# XBee_Pro_Shield.net
KiCad netlist of a schematic drawn in EAGLE
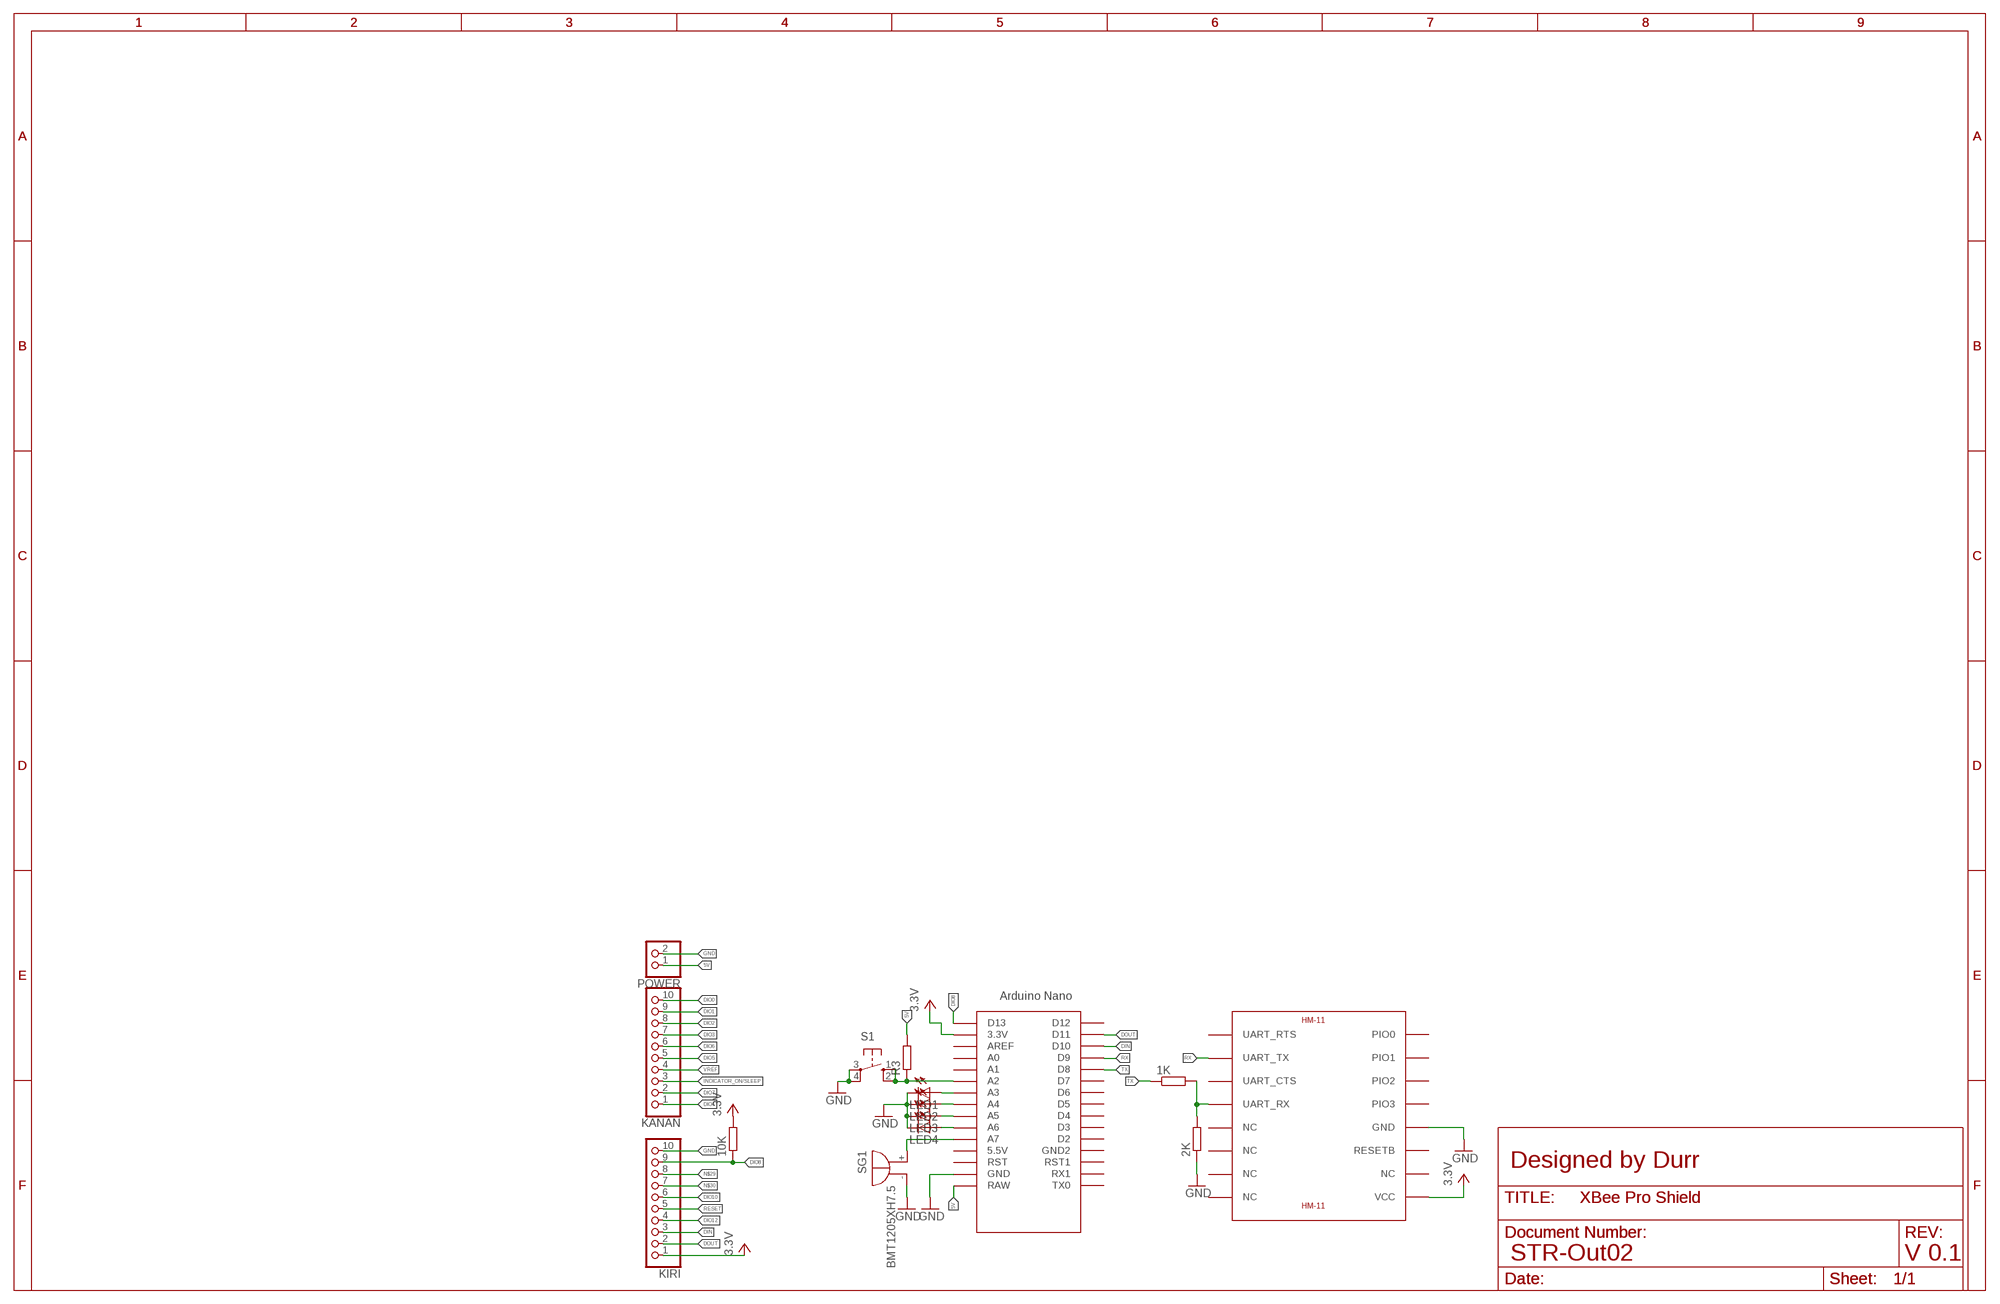
[diagram p0: schematic, sheet 1]

(export (version "E")
  (design (tool "Eeschema 10.0.6"))
  (components
    (comp (ref "1K")
      (value "R-EU_R1206")
      (footprint "eagle-import:R1206")
      (libsource (lib "eagle-import") (part "R-EU_R1206"))
    )
    (comp (ref "2K")
      (value "R-EU_R1206")
      (footprint "eagle-import:R1206")
      (libsource (lib "eagle-import") (part "R-EU_R1206"))
    )
    (comp (ref "10K")
      (value "R-EU_R1206")
      (footprint "eagle-import:R1206")
      (libsource (lib "eagle-import") (part "R-EU_R1206"))
    )
    (comp (ref "KANAN")
      (value "PINHD-1X10")
      (footprint "eagle-import:1X10")
      (libsource (lib "eagle-import") (part "PINHD-1X10"))
    )
    (comp (ref "KIRI")
      (value "PINHD-1X10")
      (footprint "eagle-import:1X10")
      (libsource (lib "eagle-import") (part "PINHD-1X10"))
    )
    (comp (ref "LED1")
      (value "LED5MM")
      (footprint "eagle-import:LED5MM")
      (libsource (lib "eagle-import") (part "LED5MM"))
    )
    (comp (ref "LED2")
      (value "LED5MM")
      (footprint "eagle-import:LED5MM")
      (libsource (lib "eagle-import") (part "LED5MM"))
    )
    (comp (ref "LED3")
      (value "LED5MM")
      (footprint "eagle-import:LED5MM")
      (libsource (lib "eagle-import") (part "LED5MM"))
    )
    (comp (ref "LED4")
      (value "LED5MM")
      (footprint "eagle-import:LED5MM")
      (libsource (lib "eagle-import") (part "LED5MM"))
    )
    (comp (ref "POWER")
      (value "PINHD-1X2")
      (footprint "eagle-import:1X02")
      (libsource (lib "eagle-import") (part "PINHD-1X2"))
    )
    (comp (ref "R3")
      (value "R-EU_R1206")
      (footprint "eagle-import:R1206")
      (libsource (lib "eagle-import") (part "R-EU_R1206"))
    )
    (comp (ref "S1")
      (value "40-XX")
      (footprint "eagle-import:B3F-40XX")
      (fields (field (name "MF") "OMRON COMPONENTS USA") (field (name "MPN") "B3F-4000"))
      (libsource (lib "eagle-import") (part "40-XX"))
    )
    (comp (ref "SG1")
      (value "BMT1205XH7.5")
      (footprint "eagle-import:BMT1205XH7.5")
      (libsource (lib "eagle-import") (part "BMT1205XH7.5"))
    )
    (comp (ref "U$1")
      (value "HM-11")
      (footprint "eagle-import:HM-11")
      (libsource (lib "eagle-import") (part "HM-11"))
    )
    (comp (ref "U$2")
      (value "NANO")
      (footprint "eagle-import:NANO")
      (libsource (lib "eagle-import") (part "NANO"))
    )
  )
  (nets
    (net (code "1") (name "3.3V") (class "Default")
      (node (ref "10K") (pin "2") (pinfunction "2_2") (pintype "passive"))
      (node (ref "KIRI") (pin "1") (pinfunction "1_1") (pintype "passive"))
      (node (ref "U$1") (pin "VCC") (pinfunction "VCC_VCC") (pintype "bidirectional"))
      (node (ref "U$2") (pin "3.3V") (pinfunction "3.3V_3.3V") (pintype "bidirectional"))
    )
    (net (code "2") (name "5V") (class "Default")
      (node (ref "POWER") (pin "1") (pinfunction "1_1") (pintype "passive"))
      (node (ref "R3") (pin "2") (pinfunction "2_2") (pintype "passive"))
      (node (ref "U$2") (pin "RAW") (pinfunction "RAW_RAW") (pintype "bidirectional"))
    )
    (net (code "3") (name "DIN") (class "Default")
      (node (ref "KIRI") (pin "3") (pinfunction "3_3") (pintype "passive"))
      (node (ref "U$2") (pin "D10") (pinfunction "D10_D10") (pintype "bidirectional"))
    )
    (net (code "4") (name "DIO0") (class "Default")
      (node (ref "KANAN") (pin "10") (pinfunction "10_10") (pintype "passive"))
    )
    (net (code "5") (name "DIO1") (class "Default")
      (node (ref "KANAN") (pin "9") (pinfunction "9_9") (pintype "passive"))
    )
    (net (code "6") (name "DIO2") (class "Default")
      (node (ref "KANAN") (pin "8") (pinfunction "8_8") (pintype "passive"))
    )
    (net (code "7") (name "DIO3") (class "Default")
      (node (ref "KANAN") (pin "7") (pinfunction "7_7") (pintype "passive"))
    )
    (net (code "8") (name "DIO4") (class "Default")
      (node (ref "KANAN") (pin "1") (pinfunction "1_1") (pintype "passive"))
    )
    (net (code "9") (name "DIO5") (class "Default")
      (node (ref "KANAN") (pin "5") (pinfunction "5_5") (pintype "passive"))
    )
    (net (code "10") (name "DIO6") (class "Default")
      (node (ref "KANAN") (pin "6") (pinfunction "6_6") (pintype "passive"))
    )
    (net (code "11") (name "DIO7") (class "Default")
      (node (ref "KANAN") (pin "2") (pinfunction "2_2") (pintype "passive"))
    )
    (net (code "12") (name "DIO8") (class "Default")
      (node (ref "10K") (pin "1") (pinfunction "1_1") (pintype "passive"))
      (node (ref "KIRI") (pin "9") (pinfunction "9_9") (pintype "passive"))
      (node (ref "U$2") (pin "D13") (pinfunction "D13_D13") (pintype "bidirectional"))
    )
    (net (code "13") (name "DIO10") (class "Default")
      (node (ref "KIRI") (pin "6") (pinfunction "6_6") (pintype "passive"))
    )
    (net (code "14") (name "DIO12") (class "Default")
      (node (ref "KIRI") (pin "4") (pinfunction "4_4") (pintype "passive"))
    )
    (net (code "15") (name "DOUT") (class "Default")
      (node (ref "KIRI") (pin "2") (pinfunction "2_2") (pintype "passive"))
      (node (ref "U$2") (pin "D11") (pinfunction "D11_D11") (pintype "bidirectional"))
    )
    (net (code "16") (name "GND") (class "Default")
      (node (ref "2K") (pin "1") (pinfunction "1_1") (pintype "passive"))
      (node (ref "KIRI") (pin "10") (pinfunction "10_10") (pintype "passive"))
      (node (ref "LED1") (pin "K") (pinfunction "C_K") (pintype "passive"))
      (node (ref "LED2") (pin "K") (pinfunction "C_K") (pintype "passive"))
      (node (ref "LED3") (pin "K") (pinfunction "C_K") (pintype "passive"))
      (node (ref "LED4") (pin "K") (pinfunction "C_K") (pintype "passive"))
      (node (ref "POWER") (pin "2") (pinfunction "2_2") (pintype "passive"))
      (node (ref "S1") (pin "3") (pinfunction "P_3") (pintype "passive"))
      (node (ref "S1") (pin "4") (pinfunction "P1_4") (pintype "passive"))
      (node (ref "SG1") (pin "-") (pinfunction "-_-") (pintype "passive"))
      (node (ref "U$1") (pin "GND") (pinfunction "GND_GND") (pintype "bidirectional"))
      (node (ref "U$2") (pin "GND") (pinfunction "GND_GND") (pintype "bidirectional"))
    )
    (net (code "17") (name "INDICATOR_ON{slash}SLEEP") (class "Default")
      (node (ref "KANAN") (pin "3") (pinfunction "3_3") (pintype "passive"))
    )
    (net (code "18") (name "N$29") (class "Default")
      (node (ref "KIRI") (pin "8") (pinfunction "8_8") (pintype "passive"))
    )
    (net (code "19") (name "N$30") (class "Default")
      (node (ref "KIRI") (pin "7") (pinfunction "7_7") (pintype "passive"))
    )
    (net (code "20") (name "Net-(1K-Pad2)") (class "Default")
      (node (ref "1K") (pin "2") (pinfunction "2_2") (pintype "passive"))
      (node (ref "2K") (pin "2") (pinfunction "2_2") (pintype "passive"))
      (node (ref "U$1") (pin "UART_RX") (pinfunction "UART_RX_UART_RX") (pintype "bidirectional"))
    )
    (net (code "21") (name "Net-(LED1-PadA)") (class "Default")
      (node (ref "LED1") (pin "A") (pinfunction "A_A") (pintype "passive"))
      (node (ref "U$2") (pin "A3") (pinfunction "A3_A3") (pintype "bidirectional"))
    )
    (net (code "22") (name "Net-(LED2-PadA)") (class "Default")
      (node (ref "LED2") (pin "A") (pinfunction "A_A") (pintype "passive"))
      (node (ref "U$2") (pin "A4") (pinfunction "A4_A4") (pintype "bidirectional"))
    )
    (net (code "23") (name "Net-(LED3-PadA)") (class "Default")
      (node (ref "LED3") (pin "A") (pinfunction "A_A") (pintype "passive"))
      (node (ref "U$2") (pin "A5") (pinfunction "A5_A5") (pintype "bidirectional"))
    )
    (net (code "24") (name "Net-(LED4-PadA)") (class "Default")
      (node (ref "LED4") (pin "A") (pinfunction "A_A") (pintype "passive"))
      (node (ref "U$2") (pin "A6") (pinfunction "A6_A6") (pintype "bidirectional"))
    )
    (net (code "25") (name "Net-(S1-S)") (class "Default")
      (node (ref "R3") (pin "1") (pinfunction "1_1") (pintype "passive"))
      (node (ref "S1") (pin "1") (pinfunction "S_1") (pintype "passive"))
      (node (ref "S1") (pin "2") (pinfunction "S1_2") (pintype "passive"))
      (node (ref "U$2") (pin "A2") (pinfunction "A2_A2") (pintype "bidirectional"))
    )
    (net (code "26") (name "Net-(SG1-Pad+)") (class "Default")
      (node (ref "SG1") (pin "+") (pinfunction "+_+") (pintype "passive"))
      (node (ref "U$2") (pin "A7") (pinfunction "A7_A7") (pintype "bidirectional"))
    )
    (net (code "27") (name "RESET") (class "Default")
      (node (ref "KIRI") (pin "5") (pinfunction "5_5") (pintype "passive"))
    )
    (net (code "28") (name "RX") (class "Default")
      (node (ref "U$1") (pin "UART_TX") (pinfunction "UART_TX_UART_TX") (pintype "bidirectional"))
      (node (ref "U$2") (pin "D9") (pinfunction "D9_D9") (pintype "bidirectional"))
    )
    (net (code "29") (name "TX") (class "Default")
      (node (ref "1K") (pin "1") (pinfunction "1_1") (pintype "passive"))
      (node (ref "U$2") (pin "D8") (pinfunction "D8_D8") (pintype "bidirectional"))
    )
    (net (code "30") (name "VREF") (class "Default")
      (node (ref "KANAN") (pin "4") (pinfunction "4_4") (pintype "passive"))
    )
    (net (code "31") (name "unconnected-(U$1-NC-PadNC@5)") (class "Default")
      (node (ref "U$1") (pin "NC@5") (pinfunction "NC_NC@5") (pintype "bidirectional"))
    )
    (net (code "32") (name "unconnected-(U$1-NC-PadNC@6)") (class "Default")
      (node (ref "U$1") (pin "NC@6") (pinfunction "NC_NC@6") (pintype "bidirectional"))
    )
    (net (code "33") (name "unconnected-(U$1-NC-PadNC@7)") (class "Default")
      (node (ref "U$1") (pin "NC@7") (pinfunction "NC_NC@7") (pintype "bidirectional"))
    )
    (net (code "34") (name "unconnected-(U$1-NC-PadNC@8)") (class "Default")
      (node (ref "U$1") (pin "NC@8") (pinfunction "NC_NC@8") (pintype "bidirectional"))
    )
    (net (code "35") (name "unconnected-(U$1-NC-PadNC@10)") (class "Default")
      (node (ref "U$1") (pin "NC@10") (pinfunction "NC_NC@10") (pintype "bidirectional"))
    )
    (net (code "36") (name "unconnected-(U$1-PadPIO0)") (class "Default")
      (node (ref "U$1") (pin "PIO0") (pinfunction "PIO0_PIO0") (pintype "bidirectional"))
    )
    (net (code "37") (name "unconnected-(U$1-PadPIO1)") (class "Default")
      (node (ref "U$1") (pin "PIO1") (pinfunction "PIO1_PIO1") (pintype "bidirectional"))
    )
    (net (code "38") (name "unconnected-(U$1-PadPIO2)") (class "Default")
      (node (ref "U$1") (pin "PIO2") (pinfunction "PIO2_PIO2") (pintype "bidirectional"))
    )
    (net (code "39") (name "unconnected-(U$1-PadPIO3)") (class "Default")
      (node (ref "U$1") (pin "PIO3") (pinfunction "PIO3_PIO3") (pintype "bidirectional"))
    )
    (net (code "40") (name "unconnected-(U$1-PadRESETB)") (class "Default")
      (node (ref "U$1") (pin "RESETB") (pinfunction "RESETB_RESETB") (pintype "bidirectional"))
    )
    (net (code "41") (name "unconnected-(U$1-PadUART_CTS)") (class "Default")
      (node (ref "U$1") (pin "UART_CTS") (pinfunction "UART_CTS_UART_CTS") (pintype "bidirectional"))
    )
    (net (code "42") (name "unconnected-(U$1-PadUART_RTS)") (class "Default")
      (node (ref "U$1") (pin "UART_RTS") (pinfunction "UART_RTS_UART_RTS") (pintype "bidirectional"))
    )
    (net (code "43") (name "unconnected-(U$2-5.5V-Pad5V)") (class "Default")
      (node (ref "U$2") (pin "5V") (pinfunction "5.5V_5V") (pintype "bidirectional"))
    )
    (net (code "44") (name "unconnected-(U$2-GND2-PadGND1)") (class "Default")
      (node (ref "U$2") (pin "GND1") (pinfunction "GND2_GND1") (pintype "bidirectional"))
    )
    (net (code "45") (name "unconnected-(U$2-PadA0)") (class "Default")
      (node (ref "U$2") (pin "A0") (pinfunction "A0_A0") (pintype "bidirectional"))
    )
    (net (code "46") (name "unconnected-(U$2-PadA1)") (class "Default")
      (node (ref "U$2") (pin "A1") (pinfunction "A1_A1") (pintype "bidirectional"))
    )
    (net (code "47") (name "unconnected-(U$2-PadAREF)") (class "Default")
      (node (ref "U$2") (pin "AREF") (pinfunction "AREF_AREF") (pintype "bidirectional"))
    )
    (net (code "48") (name "unconnected-(U$2-PadD2)") (class "Default")
      (node (ref "U$2") (pin "D2") (pinfunction "D2_D2") (pintype "bidirectional"))
    )
    (net (code "49") (name "unconnected-(U$2-PadD3)") (class "Default")
      (node (ref "U$2") (pin "D3") (pinfunction "D3_D3") (pintype "bidirectional"))
    )
    (net (code "50") (name "unconnected-(U$2-PadD4)") (class "Default")
      (node (ref "U$2") (pin "D4") (pinfunction "D4_D4") (pintype "bidirectional"))
    )
    (net (code "51") (name "unconnected-(U$2-PadD5)") (class "Default")
      (node (ref "U$2") (pin "D5") (pinfunction "D5_D5") (pintype "bidirectional"))
    )
    (net (code "52") (name "unconnected-(U$2-PadD6)") (class "Default")
      (node (ref "U$2") (pin "D6") (pinfunction "D6_D6") (pintype "bidirectional"))
    )
    (net (code "53") (name "unconnected-(U$2-PadD7)") (class "Default")
      (node (ref "U$2") (pin "D7") (pinfunction "D7_D7") (pintype "bidirectional"))
    )
    (net (code "54") (name "unconnected-(U$2-PadD12)") (class "Default")
      (node (ref "U$2") (pin "D12") (pinfunction "D12_D12") (pintype "bidirectional"))
    )
    (net (code "55") (name "unconnected-(U$2-PadICSP1)") (class "Default")
      (node (ref "U$2") (pin "ICSP1") (pinfunction "ICSP1_ICSP1") (pintype "bidirectional"))
    )
    (net (code "56") (name "unconnected-(U$2-PadICSP2)") (class "Default")
      (node (ref "U$2") (pin "ICSP2") (pinfunction "ICSP2_ICSP2") (pintype "bidirectional"))
    )
    (net (code "57") (name "unconnected-(U$2-PadICSP3)") (class "Default")
      (node (ref "U$2") (pin "ICSP3") (pinfunction "ICSP3_ICSP3") (pintype "bidirectional"))
    )
    (net (code "58") (name "unconnected-(U$2-PadICSP4)") (class "Default")
      (node (ref "U$2") (pin "ICSP4") (pinfunction "ICSP4_ICSP4") (pintype "bidirectional"))
    )
    (net (code "59") (name "unconnected-(U$2-PadICSP5)") (class "Default")
      (node (ref "U$2") (pin "ICSP5") (pinfunction "ICSP5_ICSP5") (pintype "bidirectional"))
    )
    (net (code "60") (name "unconnected-(U$2-PadICSP6)") (class "Default")
      (node (ref "U$2") (pin "ICSP6") (pinfunction "ICSP6_ICSP6") (pintype "bidirectional"))
    )
    (net (code "61") (name "unconnected-(U$2-PadRST)") (class "Default")
      (node (ref "U$2") (pin "RST") (pinfunction "RST_RST") (pintype "bidirectional"))
    )
    (net (code "62") (name "unconnected-(U$2-PadRST1)") (class "Default")
      (node (ref "U$2") (pin "RST1") (pinfunction "RST1_RST1") (pintype "bidirectional"))
    )
    (net (code "63") (name "unconnected-(U$2-PadRX1)") (class "Default")
      (node (ref "U$2") (pin "RX1") (pinfunction "RX1_RX1") (pintype "bidirectional"))
    )
    (net (code "64") (name "unconnected-(U$2-PadTX0)") (class "Default")
      (node (ref "U$2") (pin "TX0") (pinfunction "TX0_TX0") (pintype "bidirectional"))
    )
  )
)
